# Klimasensor.net
KiCad netlist of a schematic drawn in EAGLE
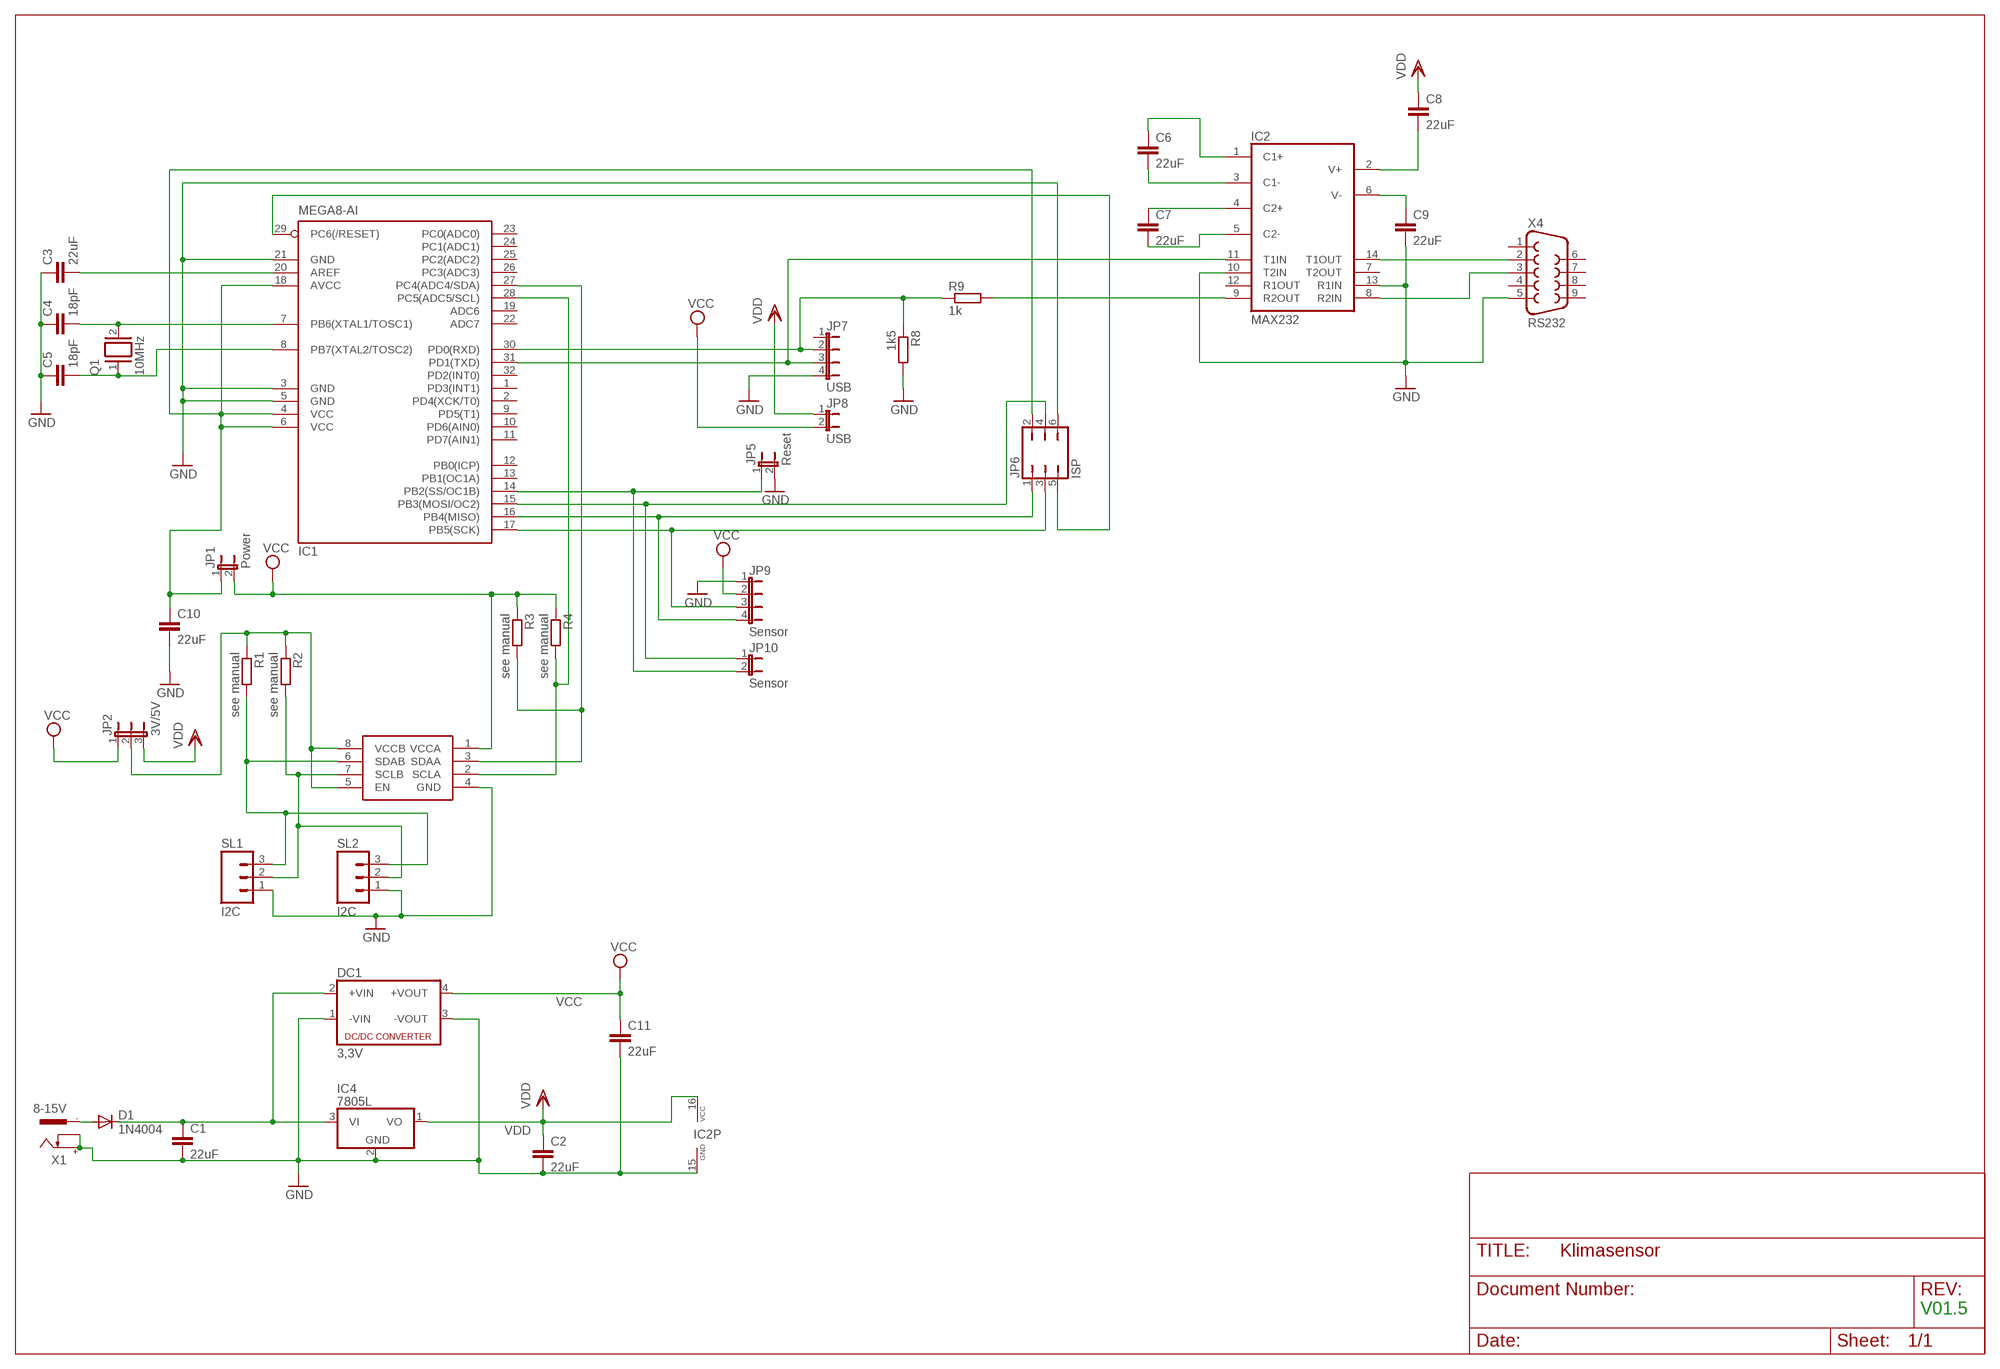
[diagram p0: schematic, sheet 1]

(export (version "E")
  (design (tool "Eeschema 10.0.6"))
  (components
    (comp (ref "C1")
      (value "22uF")
      (footprint "eagle-import:C1206")
      (libsource (lib "eagle-import") (part "C-EUC1206"))
    )
    (comp (ref "C2")
      (value "22uF")
      (footprint "eagle-import:C1206")
      (libsource (lib "eagle-import") (part "C-EUC1206"))
    )
    (comp (ref "C3")
      (value "22uF")
      (footprint "eagle-import:C1206")
      (libsource (lib "eagle-import") (part "C-EUC1206"))
    )
    (comp (ref "C4")
      (value "18pF")
      (footprint "eagle-import:C025-025X050")
      (libsource (lib "eagle-import") (part "resistor_C-EU025-025X050"))
    )
    (comp (ref "C5")
      (value "18pF")
      (footprint "eagle-import:C025-025X050")
      (libsource (lib "eagle-import") (part "resistor_C-EU025-025X050"))
    )
    (comp (ref "C6")
      (value "22uF")
      (footprint "eagle-import:C1206")
      (libsource (lib "eagle-import") (part "C-EUC1206"))
    )
    (comp (ref "C7")
      (value "22uF")
      (footprint "eagle-import:C1206")
      (libsource (lib "eagle-import") (part "C-EUC1206"))
    )
    (comp (ref "C8")
      (value "22uF")
      (footprint "eagle-import:C1206")
      (libsource (lib "eagle-import") (part "C-EUC1206"))
    )
    (comp (ref "C9")
      (value "22uF")
      (footprint "eagle-import:C1206")
      (libsource (lib "eagle-import") (part "C-EUC1206"))
    )
    (comp (ref "C10")
      (value "22uF")
      (footprint "eagle-import:C1206")
      (libsource (lib "eagle-import") (part "C-EUC1206"))
    )
    (comp (ref "C11")
      (value "22uF")
      (footprint "eagle-import:C1206")
      (libsource (lib "eagle-import") (part "C-EUC1206"))
    )
    (comp (ref "D1")
      (value "1N4004")
      (footprint "eagle-import:DO41-10")
      (libsource (lib "eagle-import") (part "1N4004"))
    )
    (comp (ref "DC1")
      (value "3,3V")
      (footprint "eagle-import:NME")
      (fields (field (name "MF") "C & D TECHNOLOGIES, INC") (field (name "MPN") "NME1205D"))
      (libsource (lib "eagle-import") (part "NME"))
    )
    (comp (ref "IC1")
      (value "MEGA8-AI")
      (footprint "eagle-import:TQFP32-08")
      (fields (field (name "MPN") "ATMEGA8-16AU"))
      (libsource (lib "eagle-import") (part "MEGA8-AI"))
    )
    (comp (ref "IC2")
      (value "MAX232")
      (footprint "eagle-import:DIL16")
      (fields (field (name "MF") "MAXIM") (field (name "MPN") "MAX232ACPE+"))
      (libsource (lib "eagle-import") (part "MAX232"))
    )
    (comp (ref "IC3")
      (value "PCA9517")
      (footprint "eagle-import:SO-08")
      (libsource (lib "eagle-import") (part "PCA9517"))
    )
    (comp (ref "IC4")
      (value "7805L")
      (footprint "eagle-import:TO92")
      (libsource (lib "eagle-import") (part "78L05"))
    )
    (comp (ref "JP1")
      (value "Power")
      (footprint "eagle-import:JP1")
      (libsource (lib "eagle-import") (part "JP1E"))
    )
    (comp (ref "JP2")
      (value "3V/5V")
      (footprint "eagle-import:JP2")
      (libsource (lib "eagle-import") (part "JP2E"))
    )
    (comp (ref "JP5")
      (value "Reset")
      (footprint "eagle-import:JP1")
      (libsource (lib "eagle-import") (part "JP1E"))
    )
    (comp (ref "JP6")
      (value "ISP")
      (footprint "eagle-import:JP3Q")
      (libsource (lib "eagle-import") (part "JP3Q"))
    )
    (comp (ref "JP7")
      (value "USB")
      (footprint "eagle-import:JP4")
      (libsource (lib "eagle-import") (part "JP4E"))
    )
    (comp (ref "JP8")
      (value "USB")
      (footprint "eagle-import:JP1")
      (libsource (lib "eagle-import") (part "JP1E"))
    )
    (comp (ref "JP9")
      (value "Sensor")
      (footprint "eagle-import:JP4")
      (libsource (lib "eagle-import") (part "JP4E"))
    )
    (comp (ref "JP10")
      (value "Sensor")
      (footprint "eagle-import:JP1")
      (libsource (lib "eagle-import") (part "JP1E"))
    )
    (comp (ref "Q1")
      (value "10MHz")
      (footprint "eagle-import:QS")
      (libsource (lib "eagle-import") (part "XTAL/S"))
    )
    (comp (ref "R1")
      (value "see manual")
      (footprint "eagle-import:R1206")
      (libsource (lib "eagle-import") (part "R-EU_R1206"))
    )
    (comp (ref "R2")
      (value "see manual")
      (footprint "eagle-import:R1206")
      (libsource (lib "eagle-import") (part "R-EU_R1206"))
    )
    (comp (ref "R3")
      (value "see manual")
      (footprint "eagle-import:R1206")
      (libsource (lib "eagle-import") (part "R-EU_R1206"))
    )
    (comp (ref "R4")
      (value "see manual")
      (footprint "eagle-import:R1206")
      (libsource (lib "eagle-import") (part "R-EU_R1206"))
    )
    (comp (ref "R8")
      (value "1k5")
      (footprint "eagle-import:R1206")
      (libsource (lib "eagle-import") (part "R-EU_R1206"))
    )
    (comp (ref "R9")
      (value "1k")
      (footprint "eagle-import:R1206")
      (libsource (lib "eagle-import") (part "R-EU_R1206"))
    )
    (comp (ref "SL1")
      (value "I2C")
      (footprint "eagle-import:03P")
      (libsource (lib "eagle-import") (part "M03"))
    )
    (comp (ref "SL2")
      (value "I2C")
      (footprint "eagle-import:03P")
      (libsource (lib "eagle-import") (part "M03"))
    )
    (comp (ref "X1")
      (value "8-15V")
      (footprint "eagle-import:737992-5")
      (libsource (lib "eagle-import") (part "737992-55"))
    )
    (comp (ref "X4")
      (value "RS232")
      (footprint "eagle-import:F09H")
      (libsource (lib "eagle-import") (part "F09H"))
    )
  )
  (nets
    (net (code "1") (name "GND") (class "Default")
      (node (ref "C1") (pin "2") (pinfunction "2_2") (pintype "passive"))
      (node (ref "C10") (pin "2") (pinfunction "2_2") (pintype "passive"))
      (node (ref "C11") (pin "2") (pinfunction "2_2") (pintype "passive"))
      (node (ref "C2") (pin "2") (pinfunction "2_2") (pintype "passive"))
      (node (ref "C3") (pin "1") (pinfunction "1_1") (pintype "passive"))
      (node (ref "C4") (pin "1") (pinfunction "1_1") (pintype "passive"))
      (node (ref "C5") (pin "1") (pinfunction "1_1") (pintype "passive"))
      (node (ref "C9") (pin "2") (pinfunction "2_2") (pintype "passive"))
      (node (ref "DC1") (pin "1") (pinfunction "-VIN_1") (pintype "passive"))
      (node (ref "DC1") (pin "3") (pinfunction "-VOUT_3") (pintype "passive"))
      (node (ref "IC1") (pin "21") (pinfunction "GND_21") (pintype "power_in"))
      (node (ref "IC1") (pin "3") (pinfunction "GND_3") (pintype "power_in"))
      (node (ref "IC1") (pin "5") (pinfunction "GND_5") (pintype "power_in"))
      (node (ref "IC2") (pin "10") (pinfunction "T2IN_10") (pintype "input"))
      (node (ref "IC2") (pin "13") (pinfunction "R1IN_13") (pintype "input"))
      (node (ref "IC2") (pin "15") (pinfunction "GND_15") (pintype "power_in"))
      (node (ref "IC3") (pin "4") (pinfunction "GND_4") (pintype "bidirectional"))
      (node (ref "IC4") (pin "2") (pinfunction "GND_2") (pintype "passive"))
      (node (ref "JP5") (pin "2") (pinfunction "2_2") (pintype "passive"))
      (node (ref "JP6") (pin "6") (pinfunction "6_6") (pintype "passive"))
      (node (ref "JP7") (pin "4") (pinfunction "4_4") (pintype "passive"))
      (node (ref "JP9") (pin "1") (pinfunction "1_1") (pintype "passive"))
      (node (ref "R8") (pin "2") (pinfunction "2_2") (pintype "passive"))
      (node (ref "SL1") (pin "1") (pinfunction "1_1") (pintype "passive"))
      (node (ref "SL2") (pin "1") (pinfunction "1_1") (pintype "passive"))
      (node (ref "X1") (pin "+") (pinfunction "+_+") (pintype "passive"))
      (node (ref "X1") (pin "K") (pinfunction "K_K") (pintype "passive"))
      (node (ref "X4") (pin "5") (pinfunction "5_5") (pintype "passive"))
    )
    (net (code "2") (name "Net-(D1-PadA)") (class "Default")
      (node (ref "D1") (pin "A") (pinfunction "A_A") (pintype "passive"))
      (node (ref "X1") (pin "-1") (pinfunction "-1_-1") (pintype "passive"))
    )
    (net (code "3") (name "Net-(DC1-+VIN)") (class "Default")
      (node (ref "C1") (pin "1") (pinfunction "1_1") (pintype "passive"))
      (node (ref "D1") (pin "C") (pinfunction "C_C") (pintype "passive"))
      (node (ref "DC1") (pin "2") (pinfunction "+VIN_2") (pintype "passive"))
      (node (ref "IC4") (pin "3") (pinfunction "VI_3") (pintype "input"))
    )
    (net (code "4") (name "Net-(IC1-AREF)") (class "Default")
      (node (ref "C3") (pin "2") (pinfunction "2_2") (pintype "passive"))
      (node (ref "IC1") (pin "20") (pinfunction "AREF_20") (pintype "passive"))
    )
    (net (code "5") (name "Net-(IC1-AVCC)") (class "Default")
      (node (ref "C10") (pin "1") (pinfunction "1_1") (pintype "passive"))
      (node (ref "IC1") (pin "18") (pinfunction "AVCC_18") (pintype "power_in"))
      (node (ref "IC1") (pin "4") (pinfunction "VCC_4") (pintype "power_in"))
      (node (ref "IC1") (pin "6") (pinfunction "VCC_6") (pintype "power_in"))
      (node (ref "JP1") (pin "1") (pinfunction "1_1") (pintype "passive"))
      (node (ref "JP6") (pin "2") (pinfunction "2_2") (pintype "passive"))
    )
    (net (code "6") (name "Net-(IC1-PB2(SS{slash}OC1B))") (class "Default")
      (node (ref "IC1") (pin "14") (pinfunction "PB2(SS/OC1B)_14") (pintype "bidirectional"))
      (node (ref "JP10") (pin "2") (pinfunction "2_2") (pintype "passive"))
      (node (ref "JP5") (pin "1") (pinfunction "1_1") (pintype "passive"))
    )
    (net (code "7") (name "Net-(IC1-PB3(MOSI{slash}OC2))") (class "Default")
      (node (ref "IC1") (pin "15") (pinfunction "PB3(MOSI/OC2)_15") (pintype "bidirectional"))
      (node (ref "JP10") (pin "1") (pinfunction "1_1") (pintype "passive"))
      (node (ref "JP6") (pin "4") (pinfunction "4_4") (pintype "passive"))
    )
    (net (code "8") (name "Net-(IC1-PB4(MISO))") (class "Default")
      (node (ref "IC1") (pin "16") (pinfunction "PB4(MISO)_16") (pintype "bidirectional"))
      (node (ref "JP6") (pin "1") (pinfunction "1_1") (pintype "passive"))
      (node (ref "JP9") (pin "4") (pinfunction "4_4") (pintype "passive"))
    )
    (net (code "9") (name "Net-(IC1-PB5(SCK))") (class "Default")
      (node (ref "IC1") (pin "17") (pinfunction "PB5(SCK)_17") (pintype "bidirectional"))
      (node (ref "JP6") (pin "3") (pinfunction "3_3") (pintype "passive"))
      (node (ref "JP9") (pin "3") (pinfunction "3_3") (pintype "passive"))
    )
    (net (code "10") (name "Net-(IC1-PB6(XTAL1{slash}TOSC1))") (class "Default")
      (node (ref "C4") (pin "2") (pinfunction "2_2") (pintype "passive"))
      (node (ref "IC1") (pin "7") (pinfunction "PB6(XTAL1/TOSC1)_7") (pintype "bidirectional"))
      (node (ref "Q1") (pin "2") (pinfunction "2_2") (pintype "passive"))
    )
    (net (code "11") (name "Net-(IC1-PB7(XTAL2{slash}TOSC2))") (class "Default")
      (node (ref "C5") (pin "2") (pinfunction "2_2") (pintype "passive"))
      (node (ref "IC1") (pin "8") (pinfunction "PB7(XTAL2/TOSC2)_8") (pintype "bidirectional"))
      (node (ref "Q1") (pin "1") (pinfunction "1_1") (pintype "passive"))
    )
    (net (code "12") (name "Net-(IC1-PC4(ADC4{slash}SDA))") (class "Default")
      (node (ref "IC1") (pin "27") (pinfunction "PC4(ADC4/SDA)_27") (pintype "bidirectional"))
      (node (ref "IC3") (pin "3") (pinfunction "SDAA_3") (pintype "bidirectional"))
      (node (ref "R3") (pin "2") (pinfunction "2_2") (pintype "passive"))
    )
    (net (code "13") (name "Net-(IC1-PC5(ADC5{slash}SCL))") (class "Default")
      (node (ref "IC1") (pin "28") (pinfunction "PC5(ADC5/SCL)_28") (pintype "bidirectional"))
      (node (ref "IC3") (pin "2") (pinfunction "SCLA_2") (pintype "bidirectional"))
      (node (ref "R4") (pin "2") (pinfunction "2_2") (pintype "passive"))
    )
    (net (code "14") (name "Net-(IC1-PC6({slash}RESET))") (class "Default")
      (node (ref "IC1") (pin "29") (pinfunction "PC6(/RESET)_29") (pintype "bidirectional"))
      (node (ref "JP6") (pin "5") (pinfunction "5_5") (pintype "passive"))
    )
    (net (code "15") (name "Net-(IC1-PD0(RXD))") (class "Default")
      (node (ref "IC1") (pin "30") (pinfunction "PD0(RXD)_30") (pintype "bidirectional"))
      (node (ref "JP7") (pin "2") (pinfunction "2_2") (pintype "passive"))
      (node (ref "R8") (pin "1") (pinfunction "1_1") (pintype "passive"))
      (node (ref "R9") (pin "1") (pinfunction "1_1") (pintype "passive"))
    )
    (net (code "16") (name "Net-(IC1-PD1(TXD))") (class "Default")
      (node (ref "IC1") (pin "31") (pinfunction "PD1(TXD)_31") (pintype "bidirectional"))
      (node (ref "IC2") (pin "11") (pinfunction "T1IN_11") (pintype "input"))
      (node (ref "JP7") (pin "3") (pinfunction "3_3") (pintype "passive"))
    )
    (net (code "17") (name "Net-(IC2A-C1+)") (class "Default")
      (node (ref "C6") (pin "1") (pinfunction "1_1") (pintype "passive"))
      (node (ref "IC2") (pin "1") (pinfunction "C1+_1") (pintype "bidirectional"))
    )
    (net (code "18") (name "Net-(IC2A-C1-)") (class "Default")
      (node (ref "C6") (pin "2") (pinfunction "2_2") (pintype "passive"))
      (node (ref "IC2") (pin "3") (pinfunction "C1-_3") (pintype "bidirectional"))
    )
    (net (code "19") (name "Net-(IC2A-C2+)") (class "Default")
      (node (ref "C7") (pin "1") (pinfunction "1_1") (pintype "passive"))
      (node (ref "IC2") (pin "4") (pinfunction "C2+_4") (pintype "bidirectional"))
    )
    (net (code "20") (name "Net-(IC2A-C2-)") (class "Default")
      (node (ref "C7") (pin "2") (pinfunction "2_2") (pintype "passive"))
      (node (ref "IC2") (pin "5") (pinfunction "C2-_5") (pintype "bidirectional"))
    )
    (net (code "21") (name "Net-(IC2A-R2IN)") (class "Default")
      (node (ref "IC2") (pin "8") (pinfunction "R2IN_8") (pintype "input"))
      (node (ref "X4") (pin "3") (pinfunction "3_3") (pintype "passive"))
    )
    (net (code "22") (name "Net-(IC2A-R2OUT)") (class "Default")
      (node (ref "IC2") (pin "9") (pinfunction "R2OUT_9") (pintype "output"))
      (node (ref "R9") (pin "2") (pinfunction "2_2") (pintype "passive"))
    )
    (net (code "23") (name "Net-(IC2A-T1OUT)") (class "Default")
      (node (ref "IC2") (pin "14") (pinfunction "T1OUT_14") (pintype "output"))
      (node (ref "X4") (pin "2") (pinfunction "2_2") (pintype "passive"))
    )
    (net (code "24") (name "Net-(IC2A-V+)") (class "Default")
      (node (ref "C8") (pin "2") (pinfunction "2_2") (pintype "passive"))
      (node (ref "IC2") (pin "2") (pinfunction "V+_2") (pintype "bidirectional"))
    )
    (net (code "25") (name "Net-(IC2A-V-)") (class "Default")
      (node (ref "C9") (pin "1") (pinfunction "1_1") (pintype "passive"))
      (node (ref "IC2") (pin "6") (pinfunction "V-_6") (pintype "bidirectional"))
    )
    (net (code "26") (name "Net-(IC3-EN)") (class "Default")
      (node (ref "IC3") (pin "5") (pinfunction "EN_5") (pintype "bidirectional"))
      (node (ref "IC3") (pin "8") (pinfunction "VCCB_8") (pintype "bidirectional"))
      (node (ref "JP2") (pin "2") (pinfunction "2_2") (pintype "passive"))
      (node (ref "R1") (pin "1") (pinfunction "1_1") (pintype "passive"))
      (node (ref "R2") (pin "1") (pinfunction "1_1") (pintype "passive"))
    )
    (net (code "27") (name "Net-(IC3-SCLB)") (class "Default")
      (node (ref "IC3") (pin "7") (pinfunction "SCLB_7") (pintype "bidirectional"))
      (node (ref "R2") (pin "2") (pinfunction "2_2") (pintype "passive"))
      (node (ref "SL1") (pin "2") (pinfunction "2_2") (pintype "passive"))
      (node (ref "SL2") (pin "2") (pinfunction "2_2") (pintype "passive"))
    )
    (net (code "28") (name "Net-(IC3-SDAB)") (class "Default")
      (node (ref "IC3") (pin "6") (pinfunction "SDAB_6") (pintype "bidirectional"))
      (node (ref "R1") (pin "2") (pinfunction "2_2") (pintype "passive"))
      (node (ref "SL1") (pin "3") (pinfunction "3_3") (pintype "passive"))
      (node (ref "SL2") (pin "3") (pinfunction "3_3") (pintype "passive"))
    )
    (net (code "29") (name "VCC") (class "Default")
      (node (ref "C11") (pin "1") (pinfunction "1_1") (pintype "passive"))
      (node (ref "DC1") (pin "4") (pinfunction "+VOUT_4") (pintype "passive"))
      (node (ref "IC3") (pin "1") (pinfunction "VCCA_1") (pintype "bidirectional"))
      (node (ref "JP1") (pin "2") (pinfunction "2_2") (pintype "passive"))
      (node (ref "JP2") (pin "1") (pinfunction "1_1") (pintype "passive"))
      (node (ref "JP8") (pin "2") (pinfunction "2_2") (pintype "passive"))
      (node (ref "JP9") (pin "2") (pinfunction "2_2") (pintype "passive"))
      (node (ref "R3") (pin "1") (pinfunction "1_1") (pintype "passive"))
      (node (ref "R4") (pin "1") (pinfunction "1_1") (pintype "passive"))
    )
    (net (code "30") (name "VDD") (class "Default")
      (node (ref "C2") (pin "1") (pinfunction "1_1") (pintype "passive"))
      (node (ref "C8") (pin "1") (pinfunction "1_1") (pintype "passive"))
      (node (ref "IC2") (pin "16") (pinfunction "VCC_16") (pintype "power_in"))
      (node (ref "IC4") (pin "1") (pinfunction "VO_1") (pintype "passive"))
      (node (ref "JP2") (pin "3") (pinfunction "3_3") (pintype "passive"))
      (node (ref "JP8") (pin "1") (pinfunction "1_1") (pintype "passive"))
    )
    (net (code "31") (name "unconnected-(IC1-ADC6-Pad19)") (class "Default")
      (node (ref "IC1") (pin "19") (pinfunction "ADC6_19") (pintype "bidirectional"))
    )
    (net (code "32") (name "unconnected-(IC1-ADC7-Pad22)") (class "Default")
      (node (ref "IC1") (pin "22") (pinfunction "ADC7_22") (pintype "bidirectional"))
    )
    (net (code "33") (name "unconnected-(IC1-PB0(ICP)-Pad12)") (class "Default")
      (node (ref "IC1") (pin "12") (pinfunction "PB0(ICP)_12") (pintype "bidirectional"))
    )
    (net (code "34") (name "unconnected-(IC1-PB1(OC1A)-Pad13)") (class "Default")
      (node (ref "IC1") (pin "13") (pinfunction "PB1(OC1A)_13") (pintype "bidirectional"))
    )
    (net (code "35") (name "unconnected-(IC1-PC0(ADC0)-Pad23)") (class "Default")
      (node (ref "IC1") (pin "23") (pinfunction "PC0(ADC0)_23") (pintype "bidirectional"))
    )
    (net (code "36") (name "unconnected-(IC1-PC1(ADC1)-Pad24)") (class "Default")
      (node (ref "IC1") (pin "24") (pinfunction "PC1(ADC1)_24") (pintype "bidirectional"))
    )
    (net (code "37") (name "unconnected-(IC1-PC2(ADC2)-Pad25)") (class "Default")
      (node (ref "IC1") (pin "25") (pinfunction "PC2(ADC2)_25") (pintype "bidirectional"))
    )
    (net (code "38") (name "unconnected-(IC1-PC3(ADC3)-Pad26)") (class "Default")
      (node (ref "IC1") (pin "26") (pinfunction "PC3(ADC3)_26") (pintype "bidirectional"))
    )
    (net (code "39") (name "unconnected-(IC1-PD2(INT0)-Pad32)") (class "Default")
      (node (ref "IC1") (pin "32") (pinfunction "PD2(INT0)_32") (pintype "bidirectional"))
    )
    (net (code "40") (name "unconnected-(IC1-PD3(INT1)-Pad1)") (class "Default")
      (node (ref "IC1") (pin "1") (pinfunction "PD3(INT1)_1") (pintype "bidirectional"))
    )
    (net (code "41") (name "unconnected-(IC1-PD4(XCK{slash}T0)-Pad2)") (class "Default")
      (node (ref "IC1") (pin "2") (pinfunction "PD4(XCK/T0)_2") (pintype "bidirectional"))
    )
    (net (code "42") (name "unconnected-(IC1-PD5(T1)-Pad9)") (class "Default")
      (node (ref "IC1") (pin "9") (pinfunction "PD5(T1)_9") (pintype "bidirectional"))
    )
    (net (code "43") (name "unconnected-(IC1-PD6(AIN0)-Pad10)") (class "Default")
      (node (ref "IC1") (pin "10") (pinfunction "PD6(AIN0)_10") (pintype "bidirectional"))
    )
    (net (code "44") (name "unconnected-(IC1-PD7(AIN1)-Pad11)") (class "Default")
      (node (ref "IC1") (pin "11") (pinfunction "PD7(AIN1)_11") (pintype "bidirectional"))
    )
    (net (code "45") (name "unconnected-(IC2A-R1OUT-Pad12)") (class "Default")
      (node (ref "IC2") (pin "12") (pinfunction "R1OUT_12") (pintype "output"))
    )
    (net (code "46") (name "unconnected-(IC2A-T2OUT-Pad7)") (class "Default")
      (node (ref "IC2") (pin "7") (pinfunction "T2OUT_7") (pintype "output"))
    )
    (net (code "47") (name "unconnected-(JP7-Pad1)") (class "Default")
      (node (ref "JP7") (pin "1") (pinfunction "1_1") (pintype "passive"))
    )
    (net (code "48") (name "unconnected-(X1-Pad-2)") (class "Default")
      (node (ref "X1") (pin "-2") (pinfunction "-2_-2") (pintype "passive"))
    )
    (net (code "49") (name "unconnected-(X4-Pad1)") (class "Default")
      (node (ref "X4") (pin "1") (pinfunction "1_1") (pintype "passive"))
    )
    (net (code "50") (name "unconnected-(X4-Pad4)") (class "Default")
      (node (ref "X4") (pin "4") (pinfunction "4_4") (pintype "passive"))
    )
    (net (code "51") (name "unconnected-(X4-Pad6)") (class "Default")
      (node (ref "X4") (pin "6") (pinfunction "6_6") (pintype "passive"))
    )
    (net (code "52") (name "unconnected-(X4-Pad7)") (class "Default")
      (node (ref "X4") (pin "7") (pinfunction "7_7") (pintype "passive"))
    )
    (net (code "53") (name "unconnected-(X4-Pad8)") (class "Default")
      (node (ref "X4") (pin "8") (pinfunction "8_8") (pintype "passive"))
    )
    (net (code "54") (name "unconnected-(X4-Pad9)") (class "Default")
      (node (ref "X4") (pin "9") (pinfunction "9_9") (pintype "passive"))
    )
  )
)
